# Control_vivero.net
KiCad netlist of a schematic drawn in EAGLE
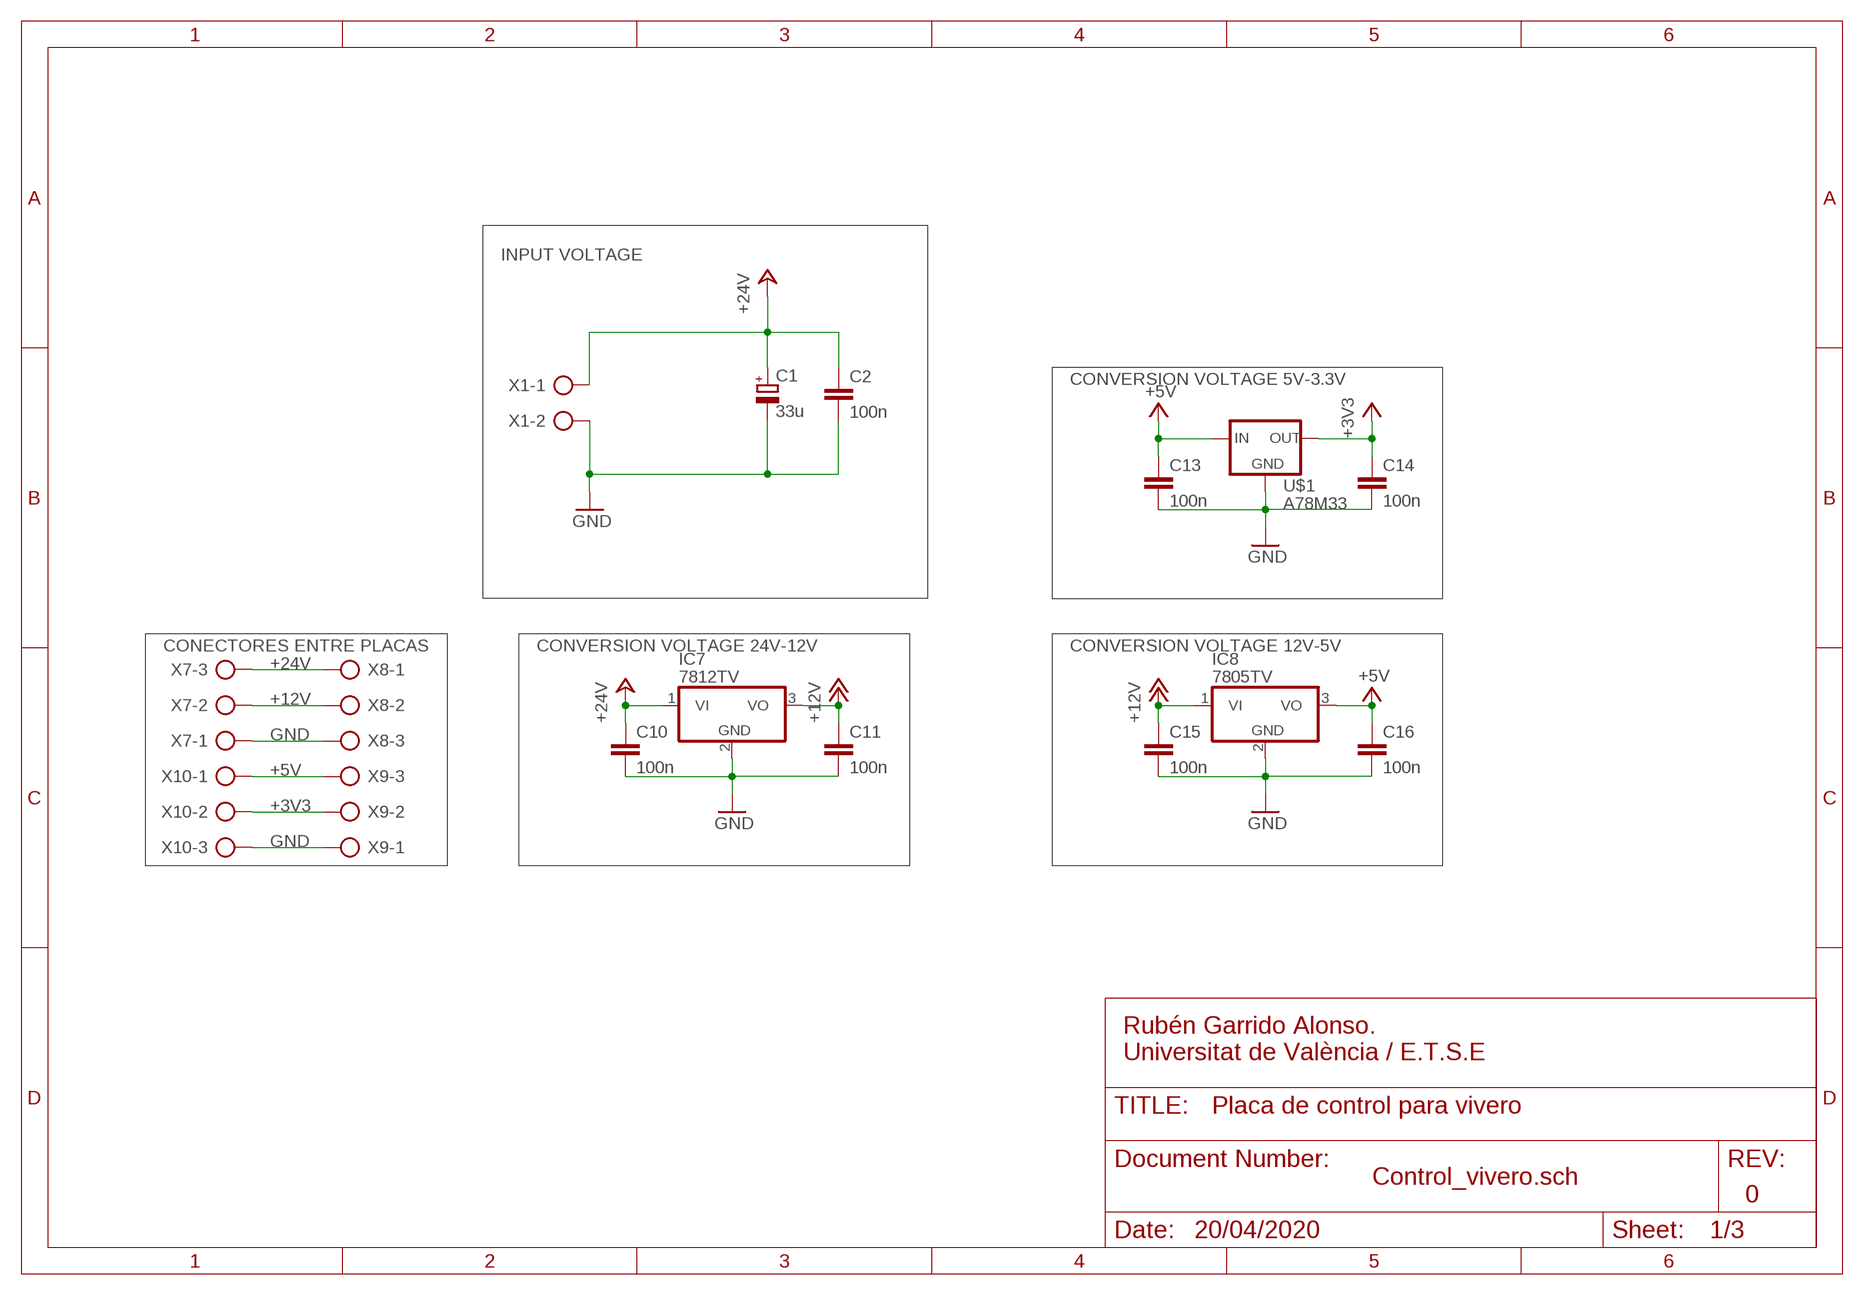
[diagram p0: schematic, sheet 1]
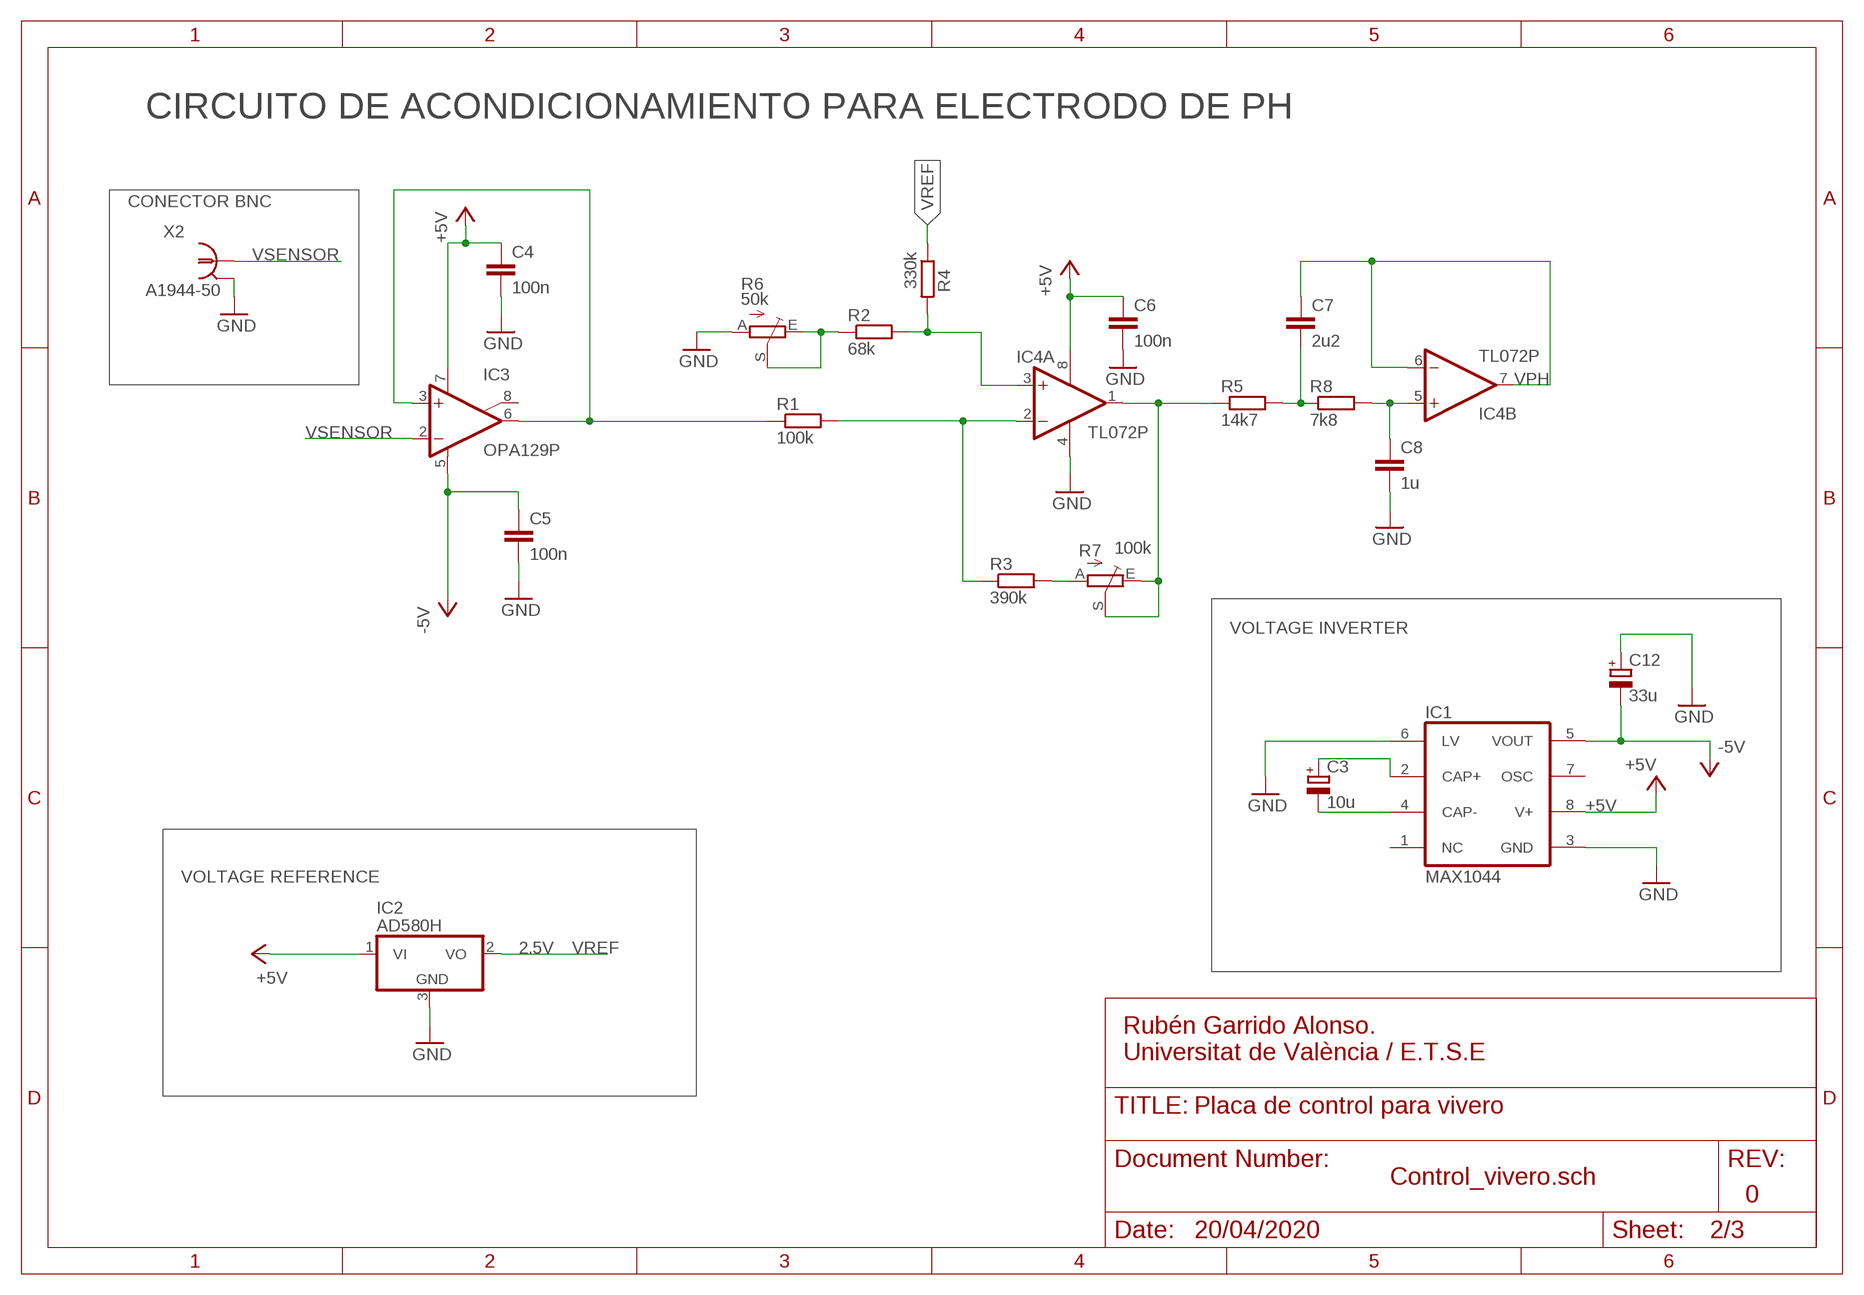
[diagram p1: schematic, sheet 2]
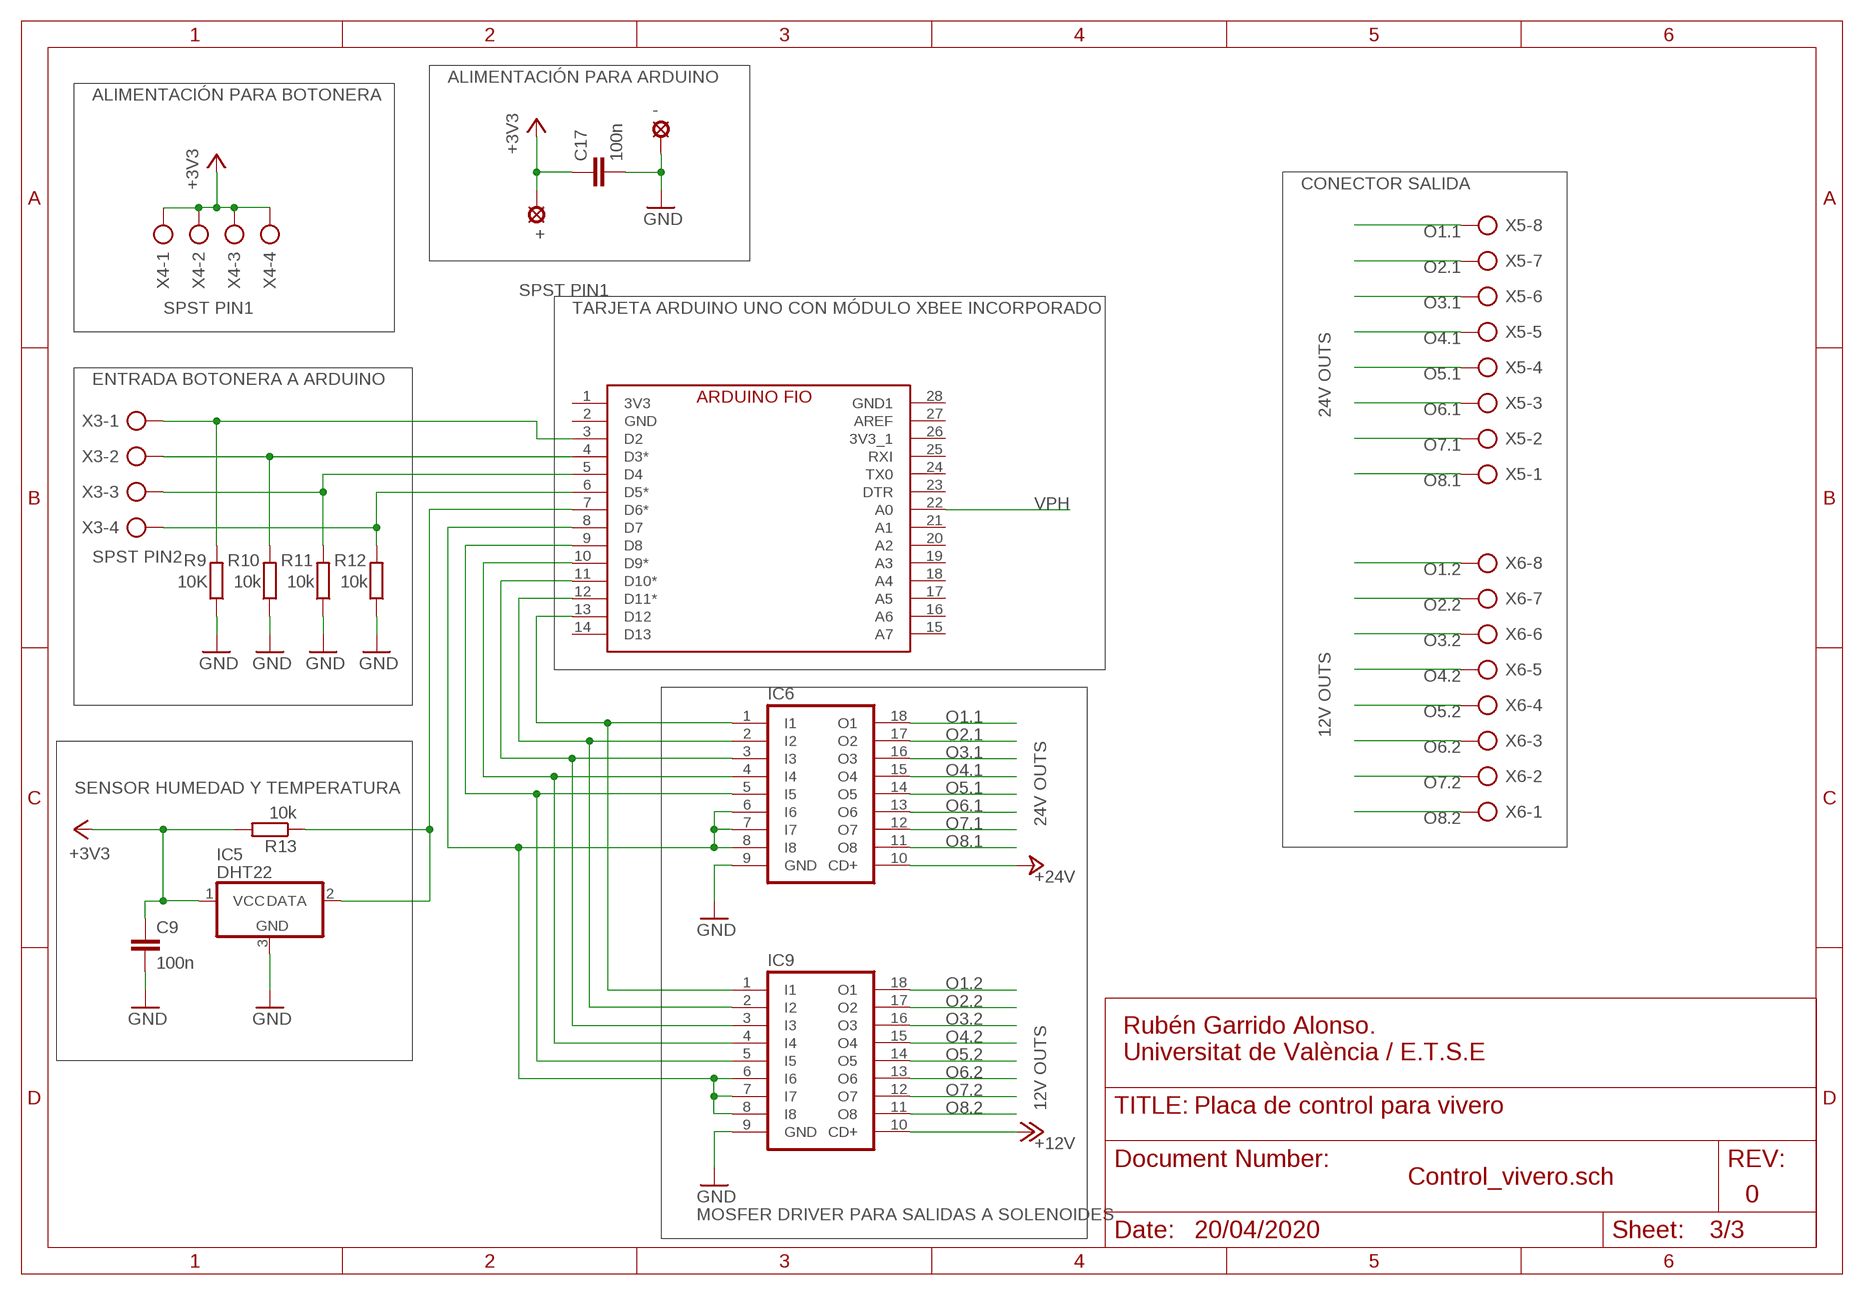
[diagram p2: schematic, sheet 3]

(export (version "E")
  (design (tool "Eeschema 10.0.6"))
  (components
    (comp (ref "+")
      (value "LSP10")
      (footprint "eagle-import:LSP10")
      (libsource (lib "eagle-import") (part "LSP10"))
    )
    (comp (ref "-")
      (value "LSP10")
      (footprint "eagle-import:LSP10")
      (libsource (lib "eagle-import") (part "LSP10"))
    )
    (comp (ref "B1")
      (value "ARDUINO_FIO")
      (footprint "eagle-import:ARDUINO_FIO_SOCKET")
      (libsource (lib "eagle-import") (part "ARDUINO_FIO"))
    )
    (comp (ref "C9")
      (value "100n")
      (footprint "eagle-import:C050-025X075")
      (libsource (lib "eagle-import") (part "C-EU050-025X075"))
    )
    (comp (ref "C17")
      (value "100n")
      (footprint "eagle-import:C050-025X075")
      (libsource (lib "eagle-import") (part "C-EU050-025X075"))
    )
    (comp (ref "IC5")
      (value "DHT22")
      (footprint "eagle-import:AK300_3")
      (libsource (lib "eagle-import") (part "DHT22"))
    )
    (comp (ref "IC6")
      (value "ULN2803A")
      (footprint "eagle-import:DIL18")
      (libsource (lib "eagle-import") (part "ULN2803A"))
    )
    (comp (ref "IC9")
      (value "ULN2803A")
      (footprint "eagle-import:DIL18")
      (libsource (lib "eagle-import") (part "ULN2803A"))
    )
    (comp (ref "R9")
      (value "10K")
      (footprint "eagle-import:0207_10")
      (libsource (lib "eagle-import") (part "R-EU_0207/10"))
    )
    (comp (ref "R10")
      (value "10k")
      (footprint "eagle-import:0207_10")
      (libsource (lib "eagle-import") (part "R-EU_0207/10"))
    )
    (comp (ref "R11")
      (value "10k")
      (footprint "eagle-import:0207_10")
      (libsource (lib "eagle-import") (part "R-EU_0207/10"))
    )
    (comp (ref "R12")
      (value "10k")
      (footprint "eagle-import:0207_10")
      (libsource (lib "eagle-import") (part "R-EU_0207/10"))
    )
    (comp (ref "R13")
      (value "10k")
      (footprint "eagle-import:0207_10")
      (libsource (lib "eagle-import") (part "R-EU_0207/10"))
    )
    (comp (ref "X3")
      (value "AK300/4")
      (footprint "eagle-import:AK300_4")
      (libsource (lib "eagle-import") (part "AK300/4"))
    )
    (comp (ref "X4")
      (value "AK300/4")
      (footprint "eagle-import:AK300_4")
      (libsource (lib "eagle-import") (part "AK300/4"))
    )
    (comp (ref "X5")
      (value "AK300/8")
      (footprint "eagle-import:AK300_8")
      (libsource (lib "eagle-import") (part "AK300/8"))
    )
    (comp (ref "X6")
      (value "AK300/8")
      (footprint "eagle-import:AK300_8")
      (libsource (lib "eagle-import") (part "AK300/8"))
    )
    (comp (ref "C1")
      (value "33u")
      (footprint "eagle-import:E2,5-7")
      (libsource (lib "eagle-import") (part "CPOL-EUE2.5-7"))
    )
    (comp (ref "C2")
      (value "100n")
      (footprint "eagle-import:C050-025X075")
      (libsource (lib "eagle-import") (part "C-EU050-025X075"))
    )
    (comp (ref "C10")
      (value "100n")
      (footprint "eagle-import:C050-025X075")
      (libsource (lib "eagle-import") (part "C-EU050-025X075"))
    )
    (comp (ref "C11")
      (value "100n")
      (footprint "eagle-import:C050-025X075")
      (libsource (lib "eagle-import") (part "C-EU050-025X075"))
    )
    (comp (ref "C13")
      (value "100n")
      (footprint "eagle-import:C050-025X075")
      (libsource (lib "eagle-import") (part "C-EU050-025X075"))
    )
    (comp (ref "C14")
      (value "100n")
      (footprint "eagle-import:C050-025X075")
      (libsource (lib "eagle-import") (part "C-EU050-025X075"))
    )
    (comp (ref "C15")
      (value "100n")
      (footprint "eagle-import:C050-025X075")
      (libsource (lib "eagle-import") (part "C-EU050-025X075"))
    )
    (comp (ref "C16")
      (value "100n")
      (footprint "eagle-import:C050-025X075")
      (libsource (lib "eagle-import") (part "C-EU050-025X075"))
    )
    (comp (ref "IC7")
      (value "7812TV")
      (footprint "eagle-import:TO220V")
      (libsource (lib "eagle-import") (part "78TV12"))
    )
    (comp (ref "IC8")
      (value "7805TV")
      (footprint "eagle-import:TO220V")
      (libsource (lib "eagle-import") (part "78TV05"))
    )
    (comp (ref "U$1")
      (value "A78M33")
      (footprint "eagle-import:TO-252")
      (libsource (lib "eagle-import") (part "A78M33"))
    )
    (comp (ref "X1")
      (value "AK500/2-H")
      (footprint "eagle-import:AK500_2-H")
      (libsource (lib "eagle-import") (part "AK500/2-H"))
    )
    (comp (ref "X7")
      (value "AK300/3")
      (footprint "eagle-import:AK300_3")
      (libsource (lib "eagle-import") (part "AK300/3"))
    )
    (comp (ref "X8")
      (value "AK300/3")
      (footprint "eagle-import:AK300_3")
      (libsource (lib "eagle-import") (part "AK300/3"))
    )
    (comp (ref "X9")
      (value "AK300/3")
      (footprint "eagle-import:AK300_3")
      (libsource (lib "eagle-import") (part "AK300/3"))
    )
    (comp (ref "X10")
      (value "AK300/3")
      (footprint "eagle-import:AK300_3")
      (libsource (lib "eagle-import") (part "AK300/3"))
    )
    (comp (ref "C3")
      (value "10u")
      (footprint "eagle-import:E2,5-6E")
      (libsource (lib "eagle-import") (part "CPOL-EUE2,5-6E"))
    )
    (comp (ref "C4")
      (value "100n")
      (footprint "eagle-import:C050-025X075")
      (libsource (lib "eagle-import") (part "C-EU050-025X075"))
    )
    (comp (ref "C5")
      (value "100n")
      (footprint "eagle-import:C050-025X075")
      (libsource (lib "eagle-import") (part "C-EU050-025X075"))
    )
    (comp (ref "C6")
      (value "100n")
      (footprint "eagle-import:C050-025X075")
      (libsource (lib "eagle-import") (part "C-EU050-025X075"))
    )
    (comp (ref "C7")
      (value "2u2")
      (footprint "eagle-import:C050-055X075")
      (libsource (lib "eagle-import") (part "C-EU050-055X075"))
    )
    (comp (ref "C8")
      (value "1u")
      (footprint "eagle-import:C050-055X075")
      (libsource (lib "eagle-import") (part "C-EU050-055X075"))
    )
    (comp (ref "C12")
      (value "33u")
      (footprint "eagle-import:E2,5-6E")
      (libsource (lib "eagle-import") (part "CPOL-EUE2,5-6E"))
    )
    (comp (ref "IC1")
      (value "MAX1044")
      (footprint "eagle-import:DIL08")
      (fields (field (name "MF") "INTERSIL") (field (name "MPN") "ICL7660CPA"))
      (libsource (lib "eagle-import") (part "MAX1044"))
    )
    (comp (ref "IC2")
      (value "AD580H")
      (footprint "eagle-import:TO39")
      (libsource (lib "eagle-import") (part "AD580H"))
    )
    (comp (ref "IC3")
      (value "OPA129P")
      (footprint "eagle-import:DIL08")
      (libsource (lib "eagle-import") (part "OPA129P"))
    )
    (comp (ref "IC4")
      (value "TL072P")
      (footprint "eagle-import:DIL08")
      (libsource (lib "eagle-import") (part "TL072P"))
    )
    (comp (ref "R1")
      (value "100k")
      (footprint "eagle-import:0207_10")
      (libsource (lib "eagle-import") (part "R-EU_0207/10"))
    )
    (comp (ref "R2")
      (value "68k")
      (footprint "eagle-import:0207_10")
      (libsource (lib "eagle-import") (part "R-EU_0207/10"))
    )
    (comp (ref "R3")
      (value "390k")
      (footprint "eagle-import:0207_10")
      (libsource (lib "eagle-import") (part "R-EU_0207/10"))
    )
    (comp (ref "R4")
      (value "330k")
      (footprint "eagle-import:0207_10")
      (libsource (lib "eagle-import") (part "R-EU_0207/10"))
    )
    (comp (ref "R5")
      (value "14k7")
      (footprint "eagle-import:0207_10")
      (libsource (lib "eagle-import") (part "R-EU_0207/10"))
    )
    (comp (ref "R6")
      (value "50k")
      (footprint "eagle-import:B25P")
      (libsource (lib "eagle-import") (part "TRIM_EU-B25P"))
    )
    (comp (ref "R7")
      (value "100k")
      (footprint "eagle-import:B25P")
      (libsource (lib "eagle-import") (part "TRIM_EU-B25P"))
    )
    (comp (ref "R8")
      (value "7k8")
      (footprint "eagle-import:0207_10")
      (libsource (lib "eagle-import") (part "R-EU_0207/10"))
    )
    (comp (ref "X2")
      (value "A1944-50")
      (footprint "eagle-import:A1944")
      (libsource (lib "eagle-import") (part "A1944-50"))
    )
  )
  (nets
    (net (code "1") (name "+3V3") (class "Default")
      (node (ref "+") (pin "MP") (pinfunction "MP_MP") (pintype "passive"))
      (node (ref "C14") (pin "1") (pinfunction "1_1") (pintype "passive"))
      (node (ref "C17") (pin "1") (pinfunction "1_1") (pintype "passive"))
      (node (ref "C9") (pin "1") (pinfunction "1_1") (pintype "passive"))
      (node (ref "IC5") (pin "1") (pinfunction "VCC_1") (pintype "power_in"))
      (node (ref "R13") (pin "2") (pinfunction "2_2") (pintype "passive"))
      (node (ref "U$1") (pin "OUT") (pinfunction "OUT_OUT") (pintype "passive"))
      (node (ref "X10") (pin "2") (pinfunction "KL_2") (pintype "passive"))
      (node (ref "X4") (pin "1") (pinfunction "KL_1") (pintype "passive"))
      (node (ref "X4") (pin "2") (pinfunction "KL_2") (pintype "passive"))
      (node (ref "X4") (pin "3") (pinfunction "KL_3") (pintype "passive"))
      (node (ref "X4") (pin "4") (pinfunction "KL_4") (pintype "passive"))
      (node (ref "X9") (pin "2") (pinfunction "KL_2") (pintype "passive"))
    )
    (net (code "2") (name "+5V") (class "Default")
      (node (ref "C13") (pin "1") (pinfunction "1_1") (pintype "passive"))
      (node (ref "C16") (pin "1") (pinfunction "1_1") (pintype "passive"))
      (node (ref "C4") (pin "1") (pinfunction "1_1") (pintype "passive"))
      (node (ref "C6") (pin "1") (pinfunction "1_1") (pintype "passive"))
      (node (ref "IC1") (pin "8") (pinfunction "V+_8") (pintype "power_in"))
      (node (ref "IC2") (pin "1") (pinfunction "VI_1") (pintype "input"))
      (node (ref "IC3") (pin "7") (pinfunction "V+_7") (pintype "power_in"))
      (node (ref "IC4") (pin "8") (pinfunction "V+_8") (pintype "power_in"))
      (node (ref "IC8") (pin "3") (pinfunction "VO_3") (pintype "passive"))
      (node (ref "U$1") (pin "IN") (pinfunction "IN_IN") (pintype "input"))
      (node (ref "X10") (pin "1") (pinfunction "KL_1") (pintype "passive"))
      (node (ref "X9") (pin "3") (pinfunction "KL_3") (pintype "passive"))
    )
    (net (code "3") (name "+12V") (class "Default")
      (node (ref "C11") (pin "1") (pinfunction "1_1") (pintype "passive"))
      (node (ref "C15") (pin "1") (pinfunction "1_1") (pintype "passive"))
      (node (ref "IC7") (pin "3") (pinfunction "VO_3") (pintype "passive"))
      (node (ref "IC8") (pin "1") (pinfunction "VI_1") (pintype "input"))
      (node (ref "IC9") (pin "10") (pinfunction "CD+_10") (pintype "passive"))
      (node (ref "X7") (pin "2") (pinfunction "KL_2") (pintype "passive"))
      (node (ref "X8") (pin "2") (pinfunction "KL_2") (pintype "passive"))
    )
    (net (code "4") (name "+24V") (class "Default")
      (node (ref "C1") (pin "+") (pinfunction "+_+") (pintype "passive"))
      (node (ref "C10") (pin "1") (pinfunction "1_1") (pintype "passive"))
      (node (ref "C2") (pin "1") (pinfunction "1_1") (pintype "passive"))
      (node (ref "IC6") (pin "10") (pinfunction "CD+_10") (pintype "passive"))
      (node (ref "IC7") (pin "1") (pinfunction "VI_1") (pintype "input"))
      (node (ref "X1") (pin "1") (pinfunction "KL_1") (pintype "passive"))
      (node (ref "X7") (pin "3") (pinfunction "KL_3") (pintype "passive"))
      (node (ref "X8") (pin "1") (pinfunction "KL_1") (pintype "passive"))
    )
    (net (code "5") (name "-5V") (class "Default")
      (node (ref "C12") (pin "-") (pinfunction "-_-") (pintype "passive"))
      (node (ref "C5") (pin "1") (pinfunction "1_1") (pintype "passive"))
      (node (ref "IC1") (pin "5") (pinfunction "VOUT_5") (pintype "power_in"))
      (node (ref "IC3") (pin "5") (pinfunction "V-_5") (pintype "power_in"))
    )
    (net (code "6") (name "GND") (class "Default")
      (node (ref "-") (pin "MP") (pinfunction "MP_MP") (pintype "passive"))
      (node (ref "C1") (pin "-") (pinfunction "-_-") (pintype "passive"))
      (node (ref "C10") (pin "2") (pinfunction "2_2") (pintype "passive"))
      (node (ref "C11") (pin "2") (pinfunction "2_2") (pintype "passive"))
      (node (ref "C12") (pin "+") (pinfunction "+_+") (pintype "passive"))
      (node (ref "C13") (pin "2") (pinfunction "2_2") (pintype "passive"))
      (node (ref "C14") (pin "2") (pinfunction "2_2") (pintype "passive"))
      (node (ref "C15") (pin "2") (pinfunction "2_2") (pintype "passive"))
      (node (ref "C16") (pin "2") (pinfunction "2_2") (pintype "passive"))
      (node (ref "C17") (pin "2") (pinfunction "2_2") (pintype "passive"))
      (node (ref "C2") (pin "2") (pinfunction "2_2") (pintype "passive"))
      (node (ref "C4") (pin "2") (pinfunction "2_2") (pintype "passive"))
      (node (ref "C5") (pin "2") (pinfunction "2_2") (pintype "passive"))
      (node (ref "C6") (pin "2") (pinfunction "2_2") (pintype "passive"))
      (node (ref "C8") (pin "2") (pinfunction "2_2") (pintype "passive"))
      (node (ref "C9") (pin "2") (pinfunction "2_2") (pintype "passive"))
      (node (ref "IC1") (pin "3") (pinfunction "GND_3") (pintype "power_in"))
      (node (ref "IC1") (pin "6") (pinfunction "LV_6") (pintype "passive"))
      (node (ref "IC2") (pin "3") (pinfunction "GND_3") (pintype "passive"))
      (node (ref "IC4") (pin "4") (pinfunction "V-_4") (pintype "power_in"))
      (node (ref "IC5") (pin "3") (pinfunction "GND_3") (pintype "power_in"))
      (node (ref "IC6") (pin "9") (pinfunction "GND_9") (pintype "power_in"))
      (node (ref "IC7") (pin "2") (pinfunction "GND_2") (pintype "passive"))
      (node (ref "IC8") (pin "2") (pinfunction "GND_2") (pintype "passive"))
      (node (ref "IC9") (pin "9") (pinfunction "GND_9") (pintype "power_in"))
      (node (ref "R10") (pin "1") (pinfunction "1_1") (pintype "passive"))
      (node (ref "R11") (pin "1") (pinfunction "1_1") (pintype "passive"))
      (node (ref "R12") (pin "1") (pinfunction "1_1") (pintype "passive"))
      (node (ref "R6") (pin "A") (pinfunction "A_A") (pintype "passive"))
      (node (ref "R9") (pin "1") (pinfunction "1_1") (pintype "passive"))
      (node (ref "U$1") (pin "COM") (pinfunction "GND_COM") (pintype "input"))
      (node (ref "X1") (pin "2") (pinfunction "KL_2") (pintype "passive"))
      (node (ref "X10") (pin "3") (pinfunction "KL_3") (pintype "passive"))
      (node (ref "X2") (pin "2") (pinfunction "2_2") (pintype "passive"))
      (node (ref "X2") (pin "3") (pinfunction "2_3") (pintype "passive"))
      (node (ref "X2") (pin "4") (pinfunction "2_4") (pintype "passive"))
      (node (ref "X2") (pin "5") (pinfunction "2_5") (pintype "passive"))
      (node (ref "X7") (pin "1") (pinfunction "KL_1") (pintype "passive"))
      (node (ref "X8") (pin "3") (pinfunction "KL_3") (pintype "passive"))
      (node (ref "X9") (pin "1") (pinfunction "KL_1") (pintype "passive"))
    )
    (net (code "7") (name "Net-(B1-D2)") (class "Default")
      (node (ref "B1") (pin "3") (pinfunction "D2_3") (pintype "passive"))
      (node (ref "R9") (pin "2") (pinfunction "2_2") (pintype "passive"))
      (node (ref "X3") (pin "1") (pinfunction "KL_1") (pintype "passive"))
    )
    (net (code "8") (name "Net-(B1-D3*)") (class "Default")
      (node (ref "B1") (pin "4") (pinfunction "D3*_4") (pintype "passive"))
      (node (ref "R10") (pin "2") (pinfunction "2_2") (pintype "passive"))
      (node (ref "X3") (pin "2") (pinfunction "KL_2") (pintype "passive"))
    )
    (net (code "9") (name "Net-(B1-D4)") (class "Default")
      (node (ref "B1") (pin "5") (pinfunction "D4_5") (pintype "passive"))
      (node (ref "R11") (pin "2") (pinfunction "2_2") (pintype "passive"))
      (node (ref "X3") (pin "3") (pinfunction "KL_3") (pintype "passive"))
    )
    (net (code "10") (name "Net-(B1-D5*)") (class "Default")
      (node (ref "B1") (pin "6") (pinfunction "D5*_6") (pintype "passive"))
      (node (ref "R12") (pin "2") (pinfunction "2_2") (pintype "passive"))
      (node (ref "X3") (pin "4") (pinfunction "KL_4") (pintype "passive"))
    )
    (net (code "11") (name "Net-(B1-D6*)") (class "Default")
      (node (ref "B1") (pin "7") (pinfunction "D6*_7") (pintype "passive"))
      (node (ref "IC5") (pin "2") (pinfunction "DATA_2") (pintype "passive"))
      (node (ref "R13") (pin "1") (pinfunction "1_1") (pintype "passive"))
    )
    (net (code "12") (name "Net-(B1-D7)") (class "Default")
      (node (ref "B1") (pin "8") (pinfunction "D7_8") (pintype "passive"))
      (node (ref "IC6") (pin "6") (pinfunction "I6_6") (pintype "input"))
      (node (ref "IC6") (pin "7") (pinfunction "I7_7") (pintype "input"))
      (node (ref "IC6") (pin "8") (pinfunction "I8_8") (pintype "input"))
      (node (ref "IC9") (pin "6") (pinfunction "I6_6") (pintype "input"))
      (node (ref "IC9") (pin "7") (pinfunction "I7_7") (pintype "input"))
      (node (ref "IC9") (pin "8") (pinfunction "I8_8") (pintype "input"))
    )
    (net (code "13") (name "Net-(B1-D8)") (class "Default")
      (node (ref "B1") (pin "9") (pinfunction "D8_9") (pintype "passive"))
      (node (ref "IC6") (pin "5") (pinfunction "I5_5") (pintype "input"))
      (node (ref "IC9") (pin "5") (pinfunction "I5_5") (pintype "input"))
    )
    (net (code "14") (name "Net-(B1-D9*)") (class "Default")
      (node (ref "B1") (pin "10") (pinfunction "D9*_10") (pintype "passive"))
      (node (ref "IC6") (pin "4") (pinfunction "I4_4") (pintype "input"))
      (node (ref "IC9") (pin "4") (pinfunction "I4_4") (pintype "input"))
    )
    (net (code "15") (name "Net-(B1-D10*)") (class "Default")
      (node (ref "B1") (pin "11") (pinfunction "D10*_11") (pintype "passive"))
      (node (ref "IC6") (pin "3") (pinfunction "I3_3") (pintype "input"))
      (node (ref "IC9") (pin "3") (pinfunction "I3_3") (pintype "input"))
    )
    (net (code "16") (name "Net-(B1-D11*)") (class "Default")
      (node (ref "B1") (pin "12") (pinfunction "D11*_12") (pintype "passive"))
      (node (ref "IC6") (pin "2") (pinfunction "I2_2") (pintype "input"))
      (node (ref "IC9") (pin "2") (pinfunction "I2_2") (pintype "input"))
    )
    (net (code "17") (name "Net-(B1-D12)") (class "Default")
      (node (ref "B1") (pin "13") (pinfunction "D12_13") (pintype "passive"))
      (node (ref "IC6") (pin "1") (pinfunction "I1_1") (pintype "input"))
      (node (ref "IC9") (pin "1") (pinfunction "I1_1") (pintype "input"))
    )
    (net (code "18") (name "Net-(C7-Pad2)") (class "Default")
      (node (ref "C7") (pin "2") (pinfunction "2_2") (pintype "passive"))
      (node (ref "R5") (pin "2") (pinfunction "2_2") (pintype "passive"))
      (node (ref "R8") (pin "1") (pinfunction "1_1") (pintype "passive"))
    )
    (net (code "19") (name "Net-(IC1-CAP+)") (class "Default")
      (node (ref "C3") (pin "+") (pinfunction "+_+") (pintype "passive"))
      (node (ref "IC1") (pin "2") (pinfunction "CAP+_2") (pintype "passive"))
    )
    (net (code "20") (name "Net-(IC1-CAP-)") (class "Default")
      (node (ref "C3") (pin "-") (pinfunction "-_-") (pintype "passive"))
      (node (ref "IC1") (pin "4") (pinfunction "CAP-_4") (pintype "passive"))
    )
    (net (code "21") (name "Net-(IC3-+IN)") (class "Default")
      (node (ref "IC3") (pin "3") (pinfunction "+IN_3") (pintype "input"))
      (node (ref "IC3") (pin "6") (pinfunction "OUT_6") (pintype "output"))
      (node (ref "R1") (pin "1") (pinfunction "1_1") (pintype "passive"))
    )
    (net (code "22") (name "Net-(IC4A-+IN)") (class "Default")
      (node (ref "IC4") (pin "3") (pinfunction "+IN_3") (pintype "input"))
      (node (ref "R2") (pin "2") (pinfunction "2_2") (pintype "passive"))
      (node (ref "R4") (pin "2") (pinfunction "2_2") (pintype "passive"))
    )
    (net (code "23") (name "Net-(IC4A--IN)") (class "Default")
      (node (ref "IC4") (pin "2") (pinfunction "-IN_2") (pintype "input"))
      (node (ref "R1") (pin "2") (pinfunction "2_2") (pintype "passive"))
      (node (ref "R3") (pin "1") (pinfunction "1_1") (pintype "passive"))
    )
    (net (code "24") (name "Net-(IC4A-OUT)") (class "Default")
      (node (ref "IC4") (pin "1") (pinfunction "OUT_1") (pintype "output"))
      (node (ref "R5") (pin "1") (pinfunction "1_1") (pintype "passive"))
      (node (ref "R7") (pin "E") (pinfunction "E_E") (pintype "passive"))
      (node (ref "R7") (pin "S") (pinfunction "S_S") (pintype "passive"))
    )
    (net (code "25") (name "Net-(IC4B-+IN)") (class "Default")
      (node (ref "C8") (pin "1") (pinfunction "1_1") (pintype "passive"))
      (node (ref "IC4") (pin "5") (pinfunction "+IN_5") (pintype "input"))
      (node (ref "R8") (pin "2") (pinfunction "2_2") (pintype "passive"))
    )
    (net (code "26") (name "Net-(R2-Pad1)") (class "Default")
      (node (ref "R2") (pin "1") (pinfunction "1_1") (pintype "passive"))
      (node (ref "R6") (pin "E") (pinfunction "E_E") (pintype "passive"))
      (node (ref "R6") (pin "S") (pinfunction "S_S") (pintype "passive"))
    )
    (net (code "27") (name "Net-(R3-Pad2)") (class "Default")
      (node (ref "R3") (pin "2") (pinfunction "2_2") (pintype "passive"))
      (node (ref "R7") (pin "A") (pinfunction "A_A") (pintype "passive"))
    )
    (net (code "28") (name "O1.1") (class "Default")
      (node (ref "IC6") (pin "18") (pinfunction "O1_18") (pintype "open_collector"))
      (node (ref "X5") (pin "8") (pinfunction "KL_8") (pintype "passive"))
    )
    (net (code "29") (name "O1.2") (class "Default")
      (node (ref "IC9") (pin "18") (pinfunction "O1_18") (pintype "open_collector"))
      (node (ref "X6") (pin "8") (pinfunction "KL_8") (pintype "passive"))
    )
    (net (code "30") (name "O2.1") (class "Default")
      (node (ref "IC6") (pin "17") (pinfunction "O2_17") (pintype "open_collector"))
      (node (ref "X5") (pin "7") (pinfunction "KL_7") (pintype "passive"))
    )
    (net (code "31") (name "O2.2") (class "Default")
      (node (ref "IC9") (pin "17") (pinfunction "O2_17") (pintype "open_collector"))
      (node (ref "X6") (pin "7") (pinfunction "KL_7") (pintype "passive"))
    )
    (net (code "32") (name "O3.1") (class "Default")
      (node (ref "IC6") (pin "16") (pinfunction "O3_16") (pintype "open_collector"))
      (node (ref "X5") (pin "6") (pinfunction "KL_6") (pintype "passive"))
    )
    (net (code "33") (name "O3.2") (class "Default")
      (node (ref "IC9") (pin "16") (pinfunction "O3_16") (pintype "open_collector"))
      (node (ref "X6") (pin "6") (pinfunction "KL_6") (pintype "passive"))
    )
    (net (code "34") (name "O4.1") (class "Default")
      (node (ref "IC6") (pin "15") (pinfunction "O4_15") (pintype "open_collector"))
      (node (ref "X5") (pin "5") (pinfunction "KL_5") (pintype "passive"))
    )
    (net (code "35") (name "O4.2") (class "Default")
      (node (ref "IC9") (pin "15") (pinfunction "O4_15") (pintype "open_collector"))
      (node (ref "X6") (pin "5") (pinfunction "KL_5") (pintype "passive"))
    )
    (net (code "36") (name "O5.1") (class "Default")
      (node (ref "IC6") (pin "14") (pinfunction "O5_14") (pintype "open_collector"))
      (node (ref "X5") (pin "4") (pinfunction "KL_4") (pintype "passive"))
    )
    (net (code "37") (name "O5.2") (class "Default")
      (node (ref "IC9") (pin "14") (pinfunction "O5_14") (pintype "open_collector"))
      (node (ref "X6") (pin "4") (pinfunction "KL_4") (pintype "passive"))
    )
    (net (code "38") (name "O6.1") (class "Default")
      (node (ref "IC6") (pin "13") (pinfunction "O6_13") (pintype "open_collector"))
      (node (ref "X5") (pin "3") (pinfunction "KL_3") (pintype "passive"))
    )
    (net (code "39") (name "O6.2") (class "Default")
      (node (ref "IC9") (pin "13") (pinfunction "O6_13") (pintype "open_collector"))
      (node (ref "X6") (pin "3") (pinfunction "KL_3") (pintype "passive"))
    )
    (net (code "40") (name "O7.1") (class "Default")
      (node (ref "IC6") (pin "12") (pinfunction "O7_12") (pintype "open_collector"))
      (node (ref "X5") (pin "2") (pinfunction "KL_2") (pintype "passive"))
    )
    (net (code "41") (name "O7.2") (class "Default")
      (node (ref "IC9") (pin "12") (pinfunction "O7_12") (pintype "open_collector"))
      (node (ref "X6") (pin "2") (pinfunction "KL_2") (pintype "passive"))
    )
    (net (code "42") (name "O8.1") (class "Default")
      (node (ref "IC6") (pin "11") (pinfunction "O8_11") (pintype "open_collector"))
      (node (ref "X5") (pin "1") (pinfunction "KL_1") (pintype "passive"))
    )
    (net (code "43") (name "O8.2") (class "Default")
      (node (ref "IC9") (pin "11") (pinfunction "O8_11") (pintype "open_collector"))
      (node (ref "X6") (pin "1") (pinfunction "KL_1") (pintype "passive"))
    )
    (net (code "44") (name "VPH") (class "Default")
      (node (ref "B1") (pin "22") (pinfunction "A0_22") (pintype "passive"))
      (node (ref "C7") (pin "1") (pinfunction "1_1") (pintype "passive"))
      (node (ref "IC4") (pin "6") (pinfunction "-IN_6") (pintype "input"))
      (node (ref "IC4") (pin "7") (pinfunction "OUT_7") (pintype "output"))
    )
    (net (code "45") (name "VREF") (class "Default")
      (node (ref "IC2") (pin "2") (pinfunction "VO_2") (pintype "passive"))
      (node (ref "R4") (pin "1") (pinfunction "1_1") (pintype "passive"))
    )
    (net (code "46") (name "VSENSOR") (class "Default")
      (node (ref "IC3") (pin "2") (pinfunction "-IN_2") (pintype "input"))
      (node (ref "X2") (pin "1") (pinfunction "1_1") (pintype "passive"))
    )
    (net (code "47") (name "unconnected-(B1-3V3-Pad1)") (class "Default")
      (node (ref "B1") (pin "1") (pinfunction "3V3_1") (pintype "passive"))
    )
    (net (code "48") (name "unconnected-(B1-3V3_1-Pad26)") (class "Default")
      (node (ref "B1") (pin "26") (pinfunction "3V3_1_26") (pintype "passive"))
    )
    (net (code "49") (name "unconnected-(B1-A1-Pad21)") (class "Default")
      (node (ref "B1") (pin "21") (pinfunction "A1_21") (pintype "passive"))
    )
    (net (code "50") (name "unconnected-(B1-A2-Pad20)") (class "Default")
      (node (ref "B1") (pin "20") (pinfunction "A2_20") (pintype "passive"))
    )
    (net (code "51") (name "unconnected-(B1-A3-Pad19)") (class "Default")
      (node (ref "B1") (pin "19") (pinfunction "A3_19") (pintype "passive"))
    )
    (net (code "52") (name "unconnected-(B1-A4-Pad18)") (class "Default")
      (node (ref "B1") (pin "18") (pinfunction "A4_18") (pintype "passive"))
    )
    (net (code "53") (name "unconnected-(B1-A5-Pad17)") (class "Default")
      (node (ref "B1") (pin "17") (pinfunction "A5_17") (pintype "passive"))
    )
    (net (code "54") (name "unconnected-(B1-A6-Pad16)") (class "Default")
      (node (ref "B1") (pin "16") (pinfunction "A6_16") (pintype "passive"))
    )
    (net (code "55") (name "unconnected-(B1-A7-Pad15)") (class "Default")
      (node (ref "B1") (pin "15") (pinfunction "A7_15") (pintype "passive"))
    )
    (net (code "56") (name "unconnected-(B1-AREF-Pad27)") (class "Default")
      (node (ref "B1") (pin "27") (pinfunction "AREF_27") (pintype "passive"))
    )
    (net (code "57") (name "unconnected-(B1-D13-Pad14)") (class "Default")
      (node (ref "B1") (pin "14") (pinfunction "D13_14") (pintype "passive"))
    )
    (net (code "58") (name "unconnected-(B1-DTR-Pad23)") (class "Default")
      (node (ref "B1") (pin "23") (pinfunction "DTR_23") (pintype "passive"))
    )
    (net (code "59") (name "unconnected-(B1-GND-Pad2)") (class "Default")
      (node (ref "B1") (pin "2") (pinfunction "GND_2") (pintype "passive"))
    )
    (net (code "60") (name "unconnected-(B1-GND1-Pad28)") (class "Default")
      (node (ref "B1") (pin "28") (pinfunction "GND1_28") (pintype "passive"))
    )
    (net (code "61") (name "unconnected-(B1-RXI-Pad25)") (class "Default")
      (node (ref "B1") (pin "25") (pinfunction "RXI_25") (pintype "passive"))
    )
    (net (code "62") (name "unconnected-(B1-TX0-Pad24)") (class "Default")
      (node (ref "B1") (pin "24") (pinfunction "TX0_24") (pintype "passive"))
    )
    (net (code "63") (name "unconnected-(IC1-NC-Pad1)") (class "Default")
      (node (ref "IC1") (pin "1") (pinfunction "NC_1") (pintype "no_connect"))
    )
    (net (code "64") (name "unconnected-(IC1-OSC-Pad7)") (class "Default")
      (node (ref "IC1") (pin "7") (pinfunction "OSC_7") (pintype "no_connect"))
    )
    (net (code "65") (name "unconnected-(IC3-SUBS-Pad8)") (class "Default")
      (node (ref "IC3") (pin "8") (pinfunction "SUBS_8") (pintype "passive"))
    )
  )
)
